# ButoMat.net
KiCad netlist of a schematic drawn in EAGLE
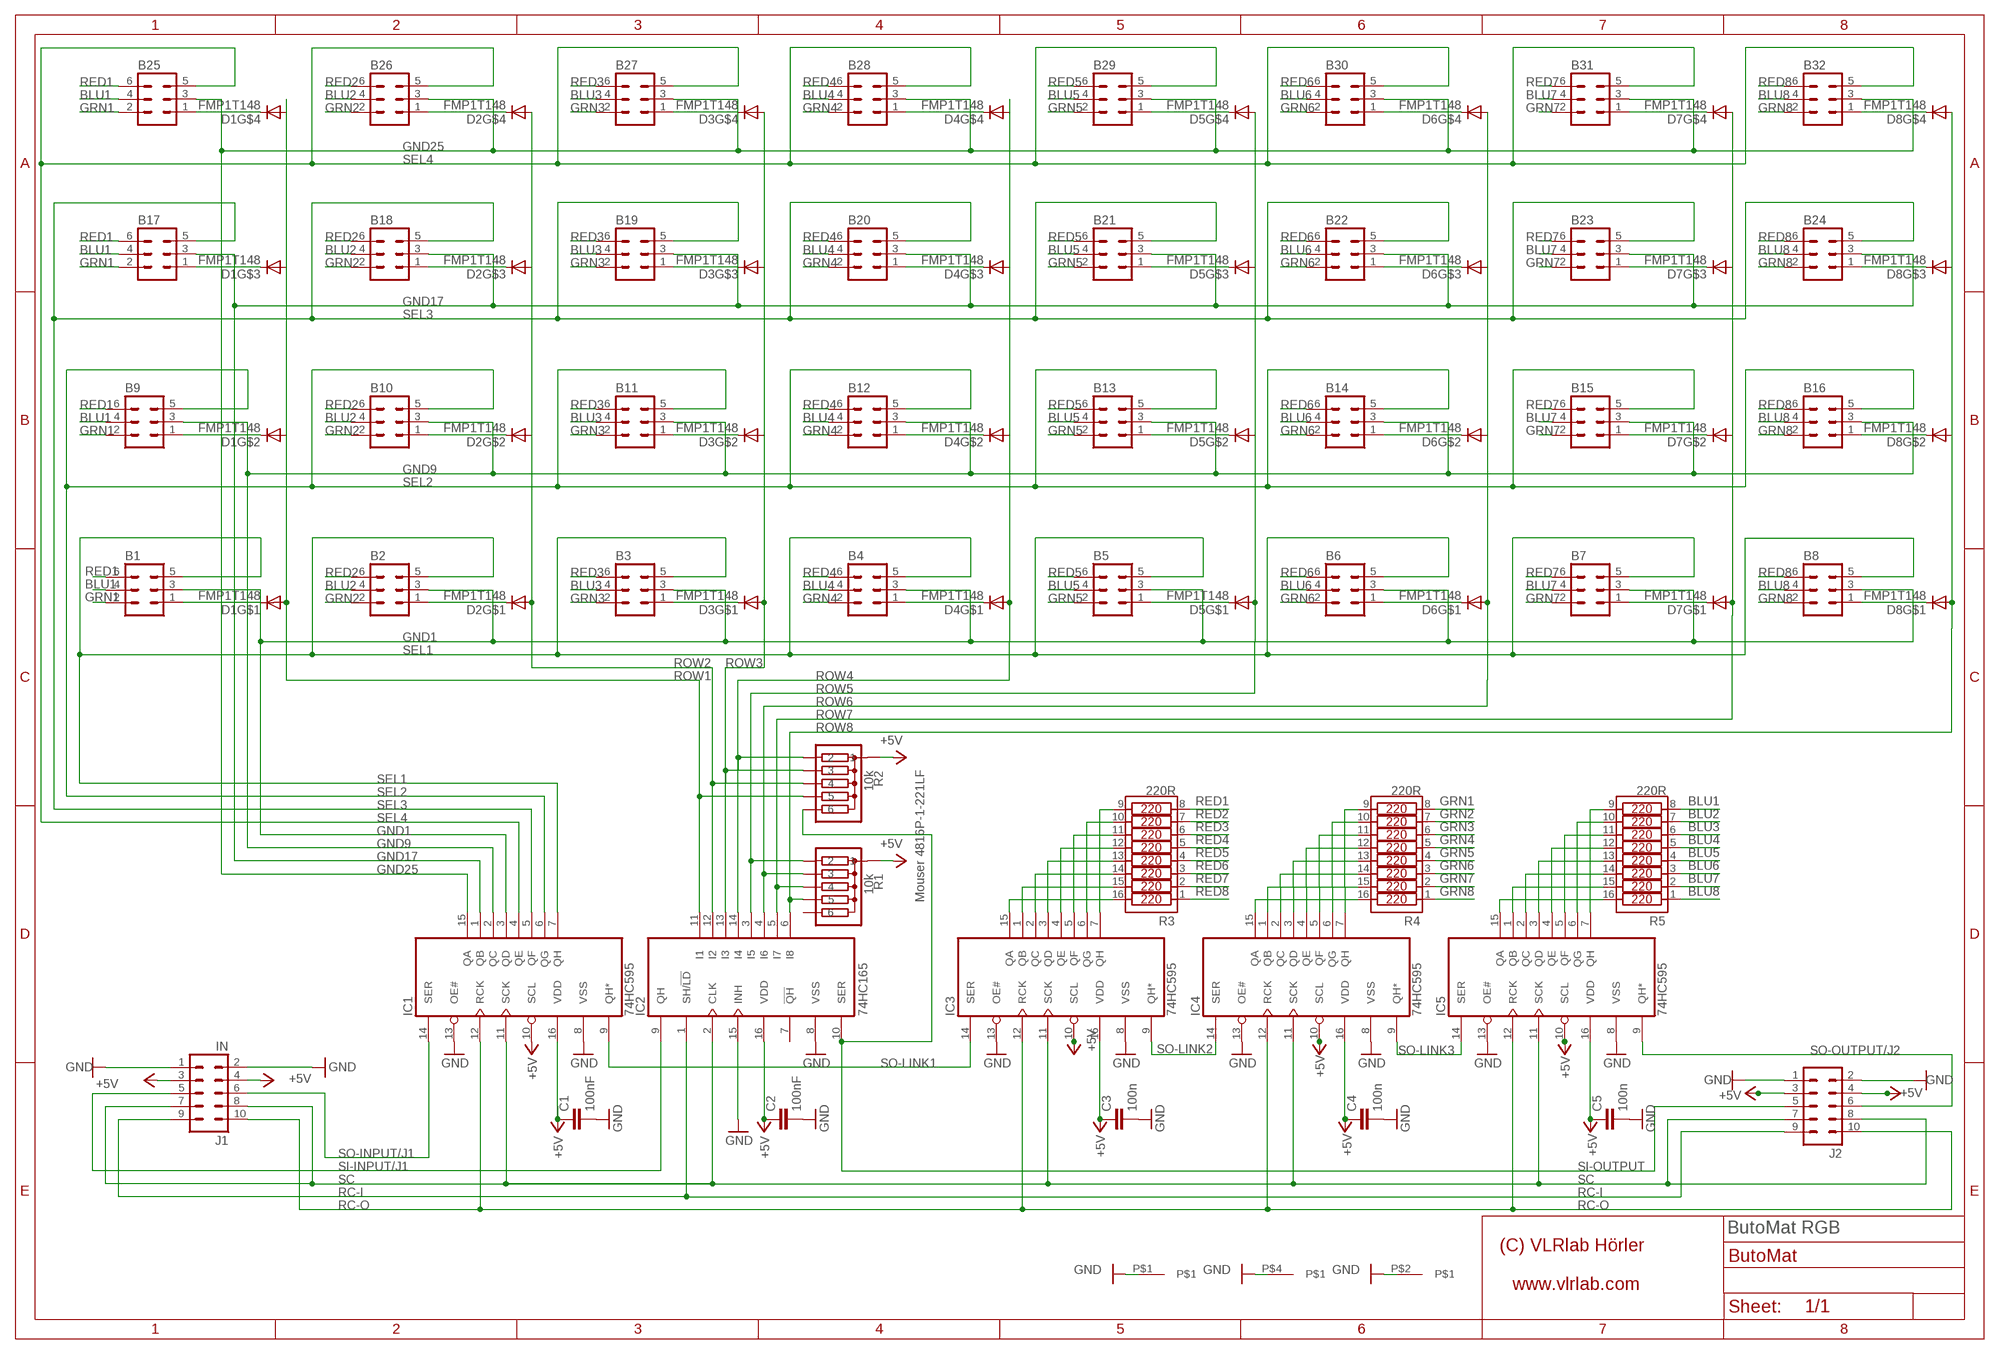
[diagram p0: schematic, sheet 1]

(export (version "E")
  (design (tool "Eeschema 10.0.6"))
  (components
    (comp (ref "B1")
      (value "ML6")
      (footprint "eagle-import:ML6")
      (libsource (lib "eagle-import") (part "ML6"))
    )
    (comp (ref "B2")
      (value "ML6")
      (footprint "eagle-import:ML6")
      (libsource (lib "eagle-import") (part "ML6"))
    )
    (comp (ref "B3")
      (value "ML6")
      (footprint "eagle-import:ML6")
      (libsource (lib "eagle-import") (part "ML6"))
    )
    (comp (ref "B4")
      (value "ML6")
      (footprint "eagle-import:ML6")
      (libsource (lib "eagle-import") (part "ML6"))
    )
    (comp (ref "B5")
      (value "ML6")
      (footprint "eagle-import:ML6")
      (libsource (lib "eagle-import") (part "ML6"))
    )
    (comp (ref "B6")
      (value "ML6")
      (footprint "eagle-import:ML6")
      (libsource (lib "eagle-import") (part "ML6"))
    )
    (comp (ref "B7")
      (value "ML6")
      (footprint "eagle-import:ML6")
      (libsource (lib "eagle-import") (part "ML6"))
    )
    (comp (ref "B8")
      (value "ML6")
      (footprint "eagle-import:ML6")
      (libsource (lib "eagle-import") (part "ML6"))
    )
    (comp (ref "B9")
      (value "ML6")
      (footprint "eagle-import:ML6")
      (libsource (lib "eagle-import") (part "ML6"))
    )
    (comp (ref "B10")
      (value "ML6")
      (footprint "eagle-import:ML6")
      (libsource (lib "eagle-import") (part "ML6"))
    )
    (comp (ref "B11")
      (value "ML6")
      (footprint "eagle-import:ML6")
      (libsource (lib "eagle-import") (part "ML6"))
    )
    (comp (ref "B12")
      (value "ML6")
      (footprint "eagle-import:ML6")
      (libsource (lib "eagle-import") (part "ML6"))
    )
    (comp (ref "B13")
      (value "ML6")
      (footprint "eagle-import:ML6")
      (libsource (lib "eagle-import") (part "ML6"))
    )
    (comp (ref "B14")
      (value "ML6")
      (footprint "eagle-import:ML6")
      (libsource (lib "eagle-import") (part "ML6"))
    )
    (comp (ref "B15")
      (value "ML6")
      (footprint "eagle-import:ML6")
      (libsource (lib "eagle-import") (part "ML6"))
    )
    (comp (ref "B16")
      (value "ML6")
      (footprint "eagle-import:ML6")
      (libsource (lib "eagle-import") (part "ML6"))
    )
    (comp (ref "B17")
      (value "ML6")
      (footprint "eagle-import:ML6")
      (libsource (lib "eagle-import") (part "ML6"))
    )
    (comp (ref "B18")
      (value "ML6")
      (footprint "eagle-import:ML6")
      (libsource (lib "eagle-import") (part "ML6"))
    )
    (comp (ref "B19")
      (value "ML6")
      (footprint "eagle-import:ML6")
      (libsource (lib "eagle-import") (part "ML6"))
    )
    (comp (ref "B20")
      (value "ML6")
      (footprint "eagle-import:ML6")
      (libsource (lib "eagle-import") (part "ML6"))
    )
    (comp (ref "B21")
      (value "ML6")
      (footprint "eagle-import:ML6")
      (libsource (lib "eagle-import") (part "ML6"))
    )
    (comp (ref "B22")
      (value "ML6")
      (footprint "eagle-import:ML6")
      (libsource (lib "eagle-import") (part "ML6"))
    )
    (comp (ref "B23")
      (value "ML6")
      (footprint "eagle-import:ML6")
      (libsource (lib "eagle-import") (part "ML6"))
    )
    (comp (ref "B24")
      (value "ML6")
      (footprint "eagle-import:ML6")
      (libsource (lib "eagle-import") (part "ML6"))
    )
    (comp (ref "B25")
      (value "ML6")
      (footprint "eagle-import:ML6")
      (libsource (lib "eagle-import") (part "ML6"))
    )
    (comp (ref "B26")
      (value "ML6")
      (footprint "eagle-import:ML6")
      (libsource (lib "eagle-import") (part "ML6"))
    )
    (comp (ref "B27")
      (value "ML6")
      (footprint "eagle-import:ML6")
      (libsource (lib "eagle-import") (part "ML6"))
    )
    (comp (ref "B28")
      (value "ML6")
      (footprint "eagle-import:ML6")
      (libsource (lib "eagle-import") (part "ML6"))
    )
    (comp (ref "B29")
      (value "ML6")
      (footprint "eagle-import:ML6")
      (libsource (lib "eagle-import") (part "ML6"))
    )
    (comp (ref "B30")
      (value "ML6")
      (footprint "eagle-import:ML6")
      (libsource (lib "eagle-import") (part "ML6"))
    )
    (comp (ref "B31")
      (value "ML6")
      (footprint "eagle-import:ML6")
      (libsource (lib "eagle-import") (part "ML6"))
    )
    (comp (ref "B32")
      (value "ML6")
      (footprint "eagle-import:ML6")
      (libsource (lib "eagle-import") (part "ML6"))
    )
    (comp (ref "C1")
      (value "100nF")
      (footprint "eagle-import:C025-030X050")
      (libsource (lib "eagle-import") (part "C-EU025-030X050"))
    )
    (comp (ref "C2")
      (value "100nF")
      (footprint "eagle-import:C025-030X050")
      (libsource (lib "eagle-import") (part "C-EU025-030X050"))
    )
    (comp (ref "C3")
      (value "100n")
      (footprint "eagle-import:C025-030X050")
      (libsource (lib "eagle-import") (part "C-EU025-030X050"))
    )
    (comp (ref "C4")
      (value "100n")
      (footprint "eagle-import:C025-030X050")
      (libsource (lib "eagle-import") (part "C-EU025-030X050"))
    )
    (comp (ref "C5")
      (value "100n")
      (footprint "eagle-import:C025-030X050")
      (libsource (lib "eagle-import") (part "C-EU025-030X050"))
    )
    (comp (ref "D1")
      (value "FMP1T148")
      (footprint "eagle-import:SC-74A")
      (libsource (lib "eagle-import") (part "FMP1T148"))
    )
    (comp (ref "D2")
      (value "FMP1T148")
      (footprint "eagle-import:SC-74A")
      (libsource (lib "eagle-import") (part "FMP1T148"))
    )
    (comp (ref "D3")
      (value "FMP1T148")
      (footprint "eagle-import:SC-74A")
      (libsource (lib "eagle-import") (part "FMP1T148"))
    )
    (comp (ref "D4")
      (value "FMP1T148")
      (footprint "eagle-import:SC-74A")
      (libsource (lib "eagle-import") (part "FMP1T148"))
    )
    (comp (ref "D5")
      (value "FMP1T148")
      (footprint "eagle-import:SC-74A")
      (libsource (lib "eagle-import") (part "FMP1T148"))
    )
    (comp (ref "D6")
      (value "FMP1T148")
      (footprint "eagle-import:SC-74A")
      (libsource (lib "eagle-import") (part "FMP1T148"))
    )
    (comp (ref "D7")
      (value "FMP1T148")
      (footprint "eagle-import:SC-74A")
      (libsource (lib "eagle-import") (part "FMP1T148"))
    )
    (comp (ref "D8")
      (value "FMP1T148")
      (footprint "eagle-import:SC-74A")
      (libsource (lib "eagle-import") (part "FMP1T148"))
    )
    (comp (ref "IC1")
      (value "74HC595")
      (footprint "eagle-import:SO16D")
      (libsource (lib "eagle-import") (part "595-541-165-uln2803_74HC595SO16D"))
    )
    (comp (ref "IC2")
      (value "74HC165")
      (footprint "eagle-import:SO16D")
      (libsource (lib "eagle-import") (part "74HC165NSO16D"))
    )
    (comp (ref "IC3")
      (value "74HC595")
      (footprint "eagle-import:SO16D")
      (libsource (lib "eagle-import") (part "595-541-165-uln2803_74HC595SO16D"))
    )
    (comp (ref "IC4")
      (value "74HC595")
      (footprint "eagle-import:SO16D")
      (libsource (lib "eagle-import") (part "595-541-165-uln2803_74HC595SO16D"))
    )
    (comp (ref "IC5")
      (value "74HC595")
      (footprint "eagle-import:SO16D")
      (libsource (lib "eagle-import") (part "595-541-165-uln2803_74HC595SO16D"))
    )
    (comp (ref "J1")
      (value "IN")
      (footprint "eagle-import:ML10")
      (libsource (lib "eagle-import") (part "ML10"))
    )
    (comp (ref "J2")
      (value "ML10")
      (footprint "eagle-import:ML10")
      (libsource (lib "eagle-import") (part "con-ml_ML10"))
    )
    (comp (ref "R1")
      (value "10k")
      (footprint "eagle-import:SIL6")
      (libsource (lib "eagle-import") (part "4306R"))
    )
    (comp (ref "R2")
      (value "10k")
      (footprint "eagle-import:SIL6")
      (libsource (lib "eagle-import") (part "4306R"))
    )
    (comp (ref "R3")
      (value "220R")
      (footprint "eagle-import:SOIC16W")
      (libsource (lib "eagle-import") (part "4816P-1SOIC16W"))
    )
    (comp (ref "R4")
      (value "220R")
      (footprint "eagle-import:SOIC16W")
      (libsource (lib "eagle-import") (part "4816P-1SOIC16W"))
    )
    (comp (ref "R5")
      (value "220R")
      (footprint "eagle-import:SOIC16W")
      (libsource (lib "eagle-import") (part "4816P-1SOIC16W"))
    )
    (comp (ref "U$1")
      (value "MIDIBOX_HALF")
      (footprint "eagle-import:MIDIBOX14X6")
      (libsource (lib "eagle-import") (part "MIDIBOX_HALF"))
    )
  )
  (nets
    (net (code "1") (name "+5V") (class "Default")
      (node (ref "C1") (pin "1") (pinfunction "1_1") (pintype "passive"))
      (node (ref "C2") (pin "1") (pinfunction "1_1") (pintype "passive"))
      (node (ref "C3") (pin "1") (pinfunction "1_1") (pintype "passive"))
      (node (ref "C4") (pin "1") (pinfunction "1_1") (pintype "passive"))
      (node (ref "C5") (pin "1") (pinfunction "1_1") (pintype "passive"))
      (node (ref "IC1") (pin "10") (pinfunction "SCL_10") (pintype "input"))
      (node (ref "IC1") (pin "16") (pinfunction "VDD_16") (pintype "power_in"))
      (node (ref "IC2") (pin "16") (pinfunction "VDD_16") (pintype "power_in"))
      (node (ref "IC3") (pin "10") (pinfunction "SCL_10") (pintype "input"))
      (node (ref "IC3") (pin "16") (pinfunction "VDD_16") (pintype "power_in"))
      (node (ref "IC4") (pin "10") (pinfunction "SCL_10") (pintype "input"))
      (node (ref "IC4") (pin "16") (pinfunction "VDD_16") (pintype "power_in"))
      (node (ref "IC5") (pin "10") (pinfunction "SCL_10") (pintype "input"))
      (node (ref "IC5") (pin "16") (pinfunction "VDD_16") (pintype "power_in"))
      (node (ref "J1") (pin "3") (pinfunction "3_3") (pintype "passive"))
      (node (ref "J1") (pin "4") (pinfunction "4_4") (pintype "passive"))
      (node (ref "J2") (pin "3") (pinfunction "3_3") (pintype "passive"))
      (node (ref "J2") (pin "4") (pinfunction "4_4") (pintype "passive"))
      (node (ref "R1") (pin "1") (pinfunction "1_1") (pintype "passive"))
      (node (ref "R2") (pin "1") (pinfunction "1_1") (pintype "passive"))
    )
    (net (code "2") (name "/BLU1") (class "Default")
      (node (ref "B1") (pin "4") (pinfunction "4_4") (pintype "passive"))
      (node (ref "B17") (pin "4") (pinfunction "4_4") (pintype "passive"))
      (node (ref "B25") (pin "4") (pinfunction "4_4") (pintype "passive"))
      (node (ref "B9") (pin "4") (pinfunction "4_4") (pintype "passive"))
      (node (ref "R5") (pin "8") (pinfunction "P$8_8") (pintype "passive"))
    )
    (net (code "3") (name "/BLU2") (class "Default")
      (node (ref "B10") (pin "4") (pinfunction "4_4") (pintype "passive"))
      (node (ref "B18") (pin "4") (pinfunction "4_4") (pintype "passive"))
      (node (ref "B2") (pin "4") (pinfunction "4_4") (pintype "passive"))
      (node (ref "B26") (pin "4") (pinfunction "4_4") (pintype "passive"))
      (node (ref "R5") (pin "7") (pinfunction "P$7_7") (pintype "passive"))
    )
    (net (code "4") (name "/BLU3") (class "Default")
      (node (ref "B11") (pin "4") (pinfunction "4_4") (pintype "passive"))
      (node (ref "B19") (pin "4") (pinfunction "4_4") (pintype "passive"))
      (node (ref "B27") (pin "4") (pinfunction "4_4") (pintype "passive"))
      (node (ref "B3") (pin "4") (pinfunction "4_4") (pintype "passive"))
      (node (ref "R5") (pin "6") (pinfunction "P$6_6") (pintype "passive"))
    )
    (net (code "5") (name "/BLU4") (class "Default")
      (node (ref "B12") (pin "4") (pinfunction "4_4") (pintype "passive"))
      (node (ref "B20") (pin "4") (pinfunction "4_4") (pintype "passive"))
      (node (ref "B28") (pin "4") (pinfunction "4_4") (pintype "passive"))
      (node (ref "B4") (pin "4") (pinfunction "4_4") (pintype "passive"))
      (node (ref "R5") (pin "5") (pinfunction "P$5_5") (pintype "passive"))
    )
    (net (code "6") (name "/BLU5") (class "Default")
      (node (ref "B13") (pin "4") (pinfunction "4_4") (pintype "passive"))
      (node (ref "B21") (pin "4") (pinfunction "4_4") (pintype "passive"))
      (node (ref "B29") (pin "4") (pinfunction "4_4") (pintype "passive"))
      (node (ref "B5") (pin "4") (pinfunction "4_4") (pintype "passive"))
      (node (ref "R5") (pin "4") (pinfunction "P$4_4") (pintype "passive"))
    )
    (net (code "7") (name "/BLU6") (class "Default")
      (node (ref "B14") (pin "4") (pinfunction "4_4") (pintype "passive"))
      (node (ref "B22") (pin "4") (pinfunction "4_4") (pintype "passive"))
      (node (ref "B30") (pin "4") (pinfunction "4_4") (pintype "passive"))
      (node (ref "B6") (pin "4") (pinfunction "4_4") (pintype "passive"))
      (node (ref "R5") (pin "3") (pinfunction "P$3_3") (pintype "passive"))
    )
    (net (code "8") (name "/BLU7") (class "Default")
      (node (ref "B15") (pin "4") (pinfunction "4_4") (pintype "passive"))
      (node (ref "B23") (pin "4") (pinfunction "4_4") (pintype "passive"))
      (node (ref "B31") (pin "4") (pinfunction "4_4") (pintype "passive"))
      (node (ref "B7") (pin "4") (pinfunction "4_4") (pintype "passive"))
      (node (ref "R5") (pin "2") (pinfunction "P$2_2") (pintype "passive"))
    )
    (net (code "9") (name "/BLU8") (class "Default")
      (node (ref "B16") (pin "4") (pinfunction "4_4") (pintype "passive"))
      (node (ref "B24") (pin "4") (pinfunction "4_4") (pintype "passive"))
      (node (ref "B32") (pin "4") (pinfunction "4_4") (pintype "passive"))
      (node (ref "B8") (pin "4") (pinfunction "4_4") (pintype "passive"))
      (node (ref "R5") (pin "1") (pinfunction "P$1_1") (pintype "passive"))
    )
    (net (code "10") (name "/GND1") (class "Default")
      (node (ref "B1") (pin "3") (pinfunction "3_3") (pintype "passive"))
      (node (ref "B2") (pin "3") (pinfunction "3_3") (pintype "passive"))
      (node (ref "B3") (pin "3") (pinfunction "3_3") (pintype "passive"))
      (node (ref "B4") (pin "3") (pinfunction "3_3") (pintype "passive"))
      (node (ref "B5") (pin "3") (pinfunction "3_3") (pintype "passive"))
      (node (ref "B6") (pin "3") (pinfunction "3_3") (pintype "passive"))
      (node (ref "B7") (pin "3") (pinfunction "3_3") (pintype "passive"))
      (node (ref "B8") (pin "3") (pinfunction "3_3") (pintype "passive"))
      (node (ref "IC1") (pin "3") (pinfunction "QD_3") (pintype "tri_state"))
    )
    (net (code "11") (name "/GND9") (class "Default")
      (node (ref "B10") (pin "3") (pinfunction "3_3") (pintype "passive"))
      (node (ref "B11") (pin "3") (pinfunction "3_3") (pintype "passive"))
      (node (ref "B12") (pin "3") (pinfunction "3_3") (pintype "passive"))
      (node (ref "B13") (pin "3") (pinfunction "3_3") (pintype "passive"))
      (node (ref "B14") (pin "3") (pinfunction "3_3") (pintype "passive"))
      (node (ref "B15") (pin "3") (pinfunction "3_3") (pintype "passive"))
      (node (ref "B16") (pin "3") (pinfunction "3_3") (pintype "passive"))
      (node (ref "B9") (pin "3") (pinfunction "3_3") (pintype "passive"))
      (node (ref "IC1") (pin "2") (pinfunction "QC_2") (pintype "tri_state"))
    )
    (net (code "12") (name "/GND17") (class "Default")
      (node (ref "B17") (pin "3") (pinfunction "3_3") (pintype "passive"))
      (node (ref "B18") (pin "3") (pinfunction "3_3") (pintype "passive"))
      (node (ref "B19") (pin "3") (pinfunction "3_3") (pintype "passive"))
      (node (ref "B20") (pin "3") (pinfunction "3_3") (pintype "passive"))
      (node (ref "B21") (pin "3") (pinfunction "3_3") (pintype "passive"))
      (node (ref "B22") (pin "3") (pinfunction "3_3") (pintype "passive"))
      (node (ref "B23") (pin "3") (pinfunction "3_3") (pintype "passive"))
      (node (ref "B24") (pin "3") (pinfunction "3_3") (pintype "passive"))
      (node (ref "IC1") (pin "1") (pinfunction "QB_1") (pintype "tri_state"))
    )
    (net (code "13") (name "/GND25") (class "Default")
      (node (ref "B25") (pin "3") (pinfunction "3_3") (pintype "passive"))
      (node (ref "B26") (pin "3") (pinfunction "3_3") (pintype "passive"))
      (node (ref "B27") (pin "3") (pinfunction "3_3") (pintype "passive"))
      (node (ref "B28") (pin "3") (pinfunction "3_3") (pintype "passive"))
      (node (ref "B29") (pin "3") (pinfunction "3_3") (pintype "passive"))
      (node (ref "B30") (pin "3") (pinfunction "3_3") (pintype "passive"))
      (node (ref "B31") (pin "3") (pinfunction "3_3") (pintype "passive"))
      (node (ref "B32") (pin "3") (pinfunction "3_3") (pintype "passive"))
      (node (ref "IC1") (pin "15") (pinfunction "QA_15") (pintype "tri_state"))
    )
    (net (code "14") (name "/GRN1") (class "Default")
      (node (ref "B1") (pin "2") (pinfunction "2_2") (pintype "passive"))
      (node (ref "B17") (pin "2") (pinfunction "2_2") (pintype "passive"))
      (node (ref "B25") (pin "2") (pinfunction "2_2") (pintype "passive"))
      (node (ref "B9") (pin "2") (pinfunction "2_2") (pintype "passive"))
      (node (ref "R4") (pin "8") (pinfunction "P$8_8") (pintype "passive"))
    )
    (net (code "15") (name "/GRN2") (class "Default")
      (node (ref "B10") (pin "2") (pinfunction "2_2") (pintype "passive"))
      (node (ref "B18") (pin "2") (pinfunction "2_2") (pintype "passive"))
      (node (ref "B2") (pin "2") (pinfunction "2_2") (pintype "passive"))
      (node (ref "B26") (pin "2") (pinfunction "2_2") (pintype "passive"))
      (node (ref "R4") (pin "7") (pinfunction "P$7_7") (pintype "passive"))
    )
    (net (code "16") (name "/GRN3") (class "Default")
      (node (ref "B11") (pin "2") (pinfunction "2_2") (pintype "passive"))
      (node (ref "B19") (pin "2") (pinfunction "2_2") (pintype "passive"))
      (node (ref "B27") (pin "2") (pinfunction "2_2") (pintype "passive"))
      (node (ref "B3") (pin "2") (pinfunction "2_2") (pintype "passive"))
      (node (ref "R4") (pin "6") (pinfunction "P$6_6") (pintype "passive"))
    )
    (net (code "17") (name "/GRN4") (class "Default")
      (node (ref "B12") (pin "2") (pinfunction "2_2") (pintype "passive"))
      (node (ref "B20") (pin "2") (pinfunction "2_2") (pintype "passive"))
      (node (ref "B28") (pin "2") (pinfunction "2_2") (pintype "passive"))
      (node (ref "B4") (pin "2") (pinfunction "2_2") (pintype "passive"))
      (node (ref "R4") (pin "5") (pinfunction "P$5_5") (pintype "passive"))
    )
    (net (code "18") (name "/GRN5") (class "Default")
      (node (ref "B13") (pin "2") (pinfunction "2_2") (pintype "passive"))
      (node (ref "B21") (pin "2") (pinfunction "2_2") (pintype "passive"))
      (node (ref "B29") (pin "2") (pinfunction "2_2") (pintype "passive"))
      (node (ref "B5") (pin "2") (pinfunction "2_2") (pintype "passive"))
      (node (ref "R4") (pin "4") (pinfunction "P$4_4") (pintype "passive"))
    )
    (net (code "19") (name "/GRN6") (class "Default")
      (node (ref "B14") (pin "2") (pinfunction "2_2") (pintype "passive"))
      (node (ref "B22") (pin "2") (pinfunction "2_2") (pintype "passive"))
      (node (ref "B30") (pin "2") (pinfunction "2_2") (pintype "passive"))
      (node (ref "B6") (pin "2") (pinfunction "2_2") (pintype "passive"))
      (node (ref "R4") (pin "3") (pinfunction "P$3_3") (pintype "passive"))
    )
    (net (code "20") (name "/GRN7") (class "Default")
      (node (ref "B15") (pin "2") (pinfunction "2_2") (pintype "passive"))
      (node (ref "B23") (pin "2") (pinfunction "2_2") (pintype "passive"))
      (node (ref "B31") (pin "2") (pinfunction "2_2") (pintype "passive"))
      (node (ref "B7") (pin "2") (pinfunction "2_2") (pintype "passive"))
      (node (ref "R4") (pin "2") (pinfunction "P$2_2") (pintype "passive"))
    )
    (net (code "21") (name "/GRN8") (class "Default")
      (node (ref "B16") (pin "2") (pinfunction "2_2") (pintype "passive"))
      (node (ref "B24") (pin "2") (pinfunction "2_2") (pintype "passive"))
      (node (ref "B32") (pin "2") (pinfunction "2_2") (pintype "passive"))
      (node (ref "B8") (pin "2") (pinfunction "2_2") (pintype "passive"))
      (node (ref "R4") (pin "1") (pinfunction "P$1_1") (pintype "passive"))
    )
    (net (code "22") (name "/RC-I") (class "Default")
      (node (ref "IC2") (pin "1") (pinfunction "SH/~{LD}_1") (pintype "input"))
      (node (ref "J1") (pin "9") (pinfunction "9_9") (pintype "passive"))
      (node (ref "J2") (pin "9") (pinfunction "9_9") (pintype "passive"))
    )
    (net (code "23") (name "/RC-O") (class "Default")
      (node (ref "IC1") (pin "12") (pinfunction "RCK_12") (pintype "input"))
      (node (ref "IC3") (pin "12") (pinfunction "RCK_12") (pintype "input"))
      (node (ref "IC4") (pin "12") (pinfunction "RCK_12") (pintype "input"))
      (node (ref "IC5") (pin "12") (pinfunction "RCK_12") (pintype "input"))
      (node (ref "J1") (pin "10") (pinfunction "10_10") (pintype "passive"))
      (node (ref "J2") (pin "10") (pinfunction "10_10") (pintype "passive"))
    )
    (net (code "24") (name "/RED1") (class "Default")
      (node (ref "B1") (pin "6") (pinfunction "6_6") (pintype "passive"))
      (node (ref "B17") (pin "6") (pinfunction "6_6") (pintype "passive"))
      (node (ref "B25") (pin "6") (pinfunction "6_6") (pintype "passive"))
      (node (ref "B9") (pin "6") (pinfunction "6_6") (pintype "passive"))
      (node (ref "R3") (pin "8") (pinfunction "P$8_8") (pintype "passive"))
    )
    (net (code "25") (name "/RED2") (class "Default")
      (node (ref "B10") (pin "6") (pinfunction "6_6") (pintype "passive"))
      (node (ref "B18") (pin "6") (pinfunction "6_6") (pintype "passive"))
      (node (ref "B2") (pin "6") (pinfunction "6_6") (pintype "passive"))
      (node (ref "B26") (pin "6") (pinfunction "6_6") (pintype "passive"))
      (node (ref "R3") (pin "7") (pinfunction "P$7_7") (pintype "passive"))
    )
    (net (code "26") (name "/RED3") (class "Default")
      (node (ref "B11") (pin "6") (pinfunction "6_6") (pintype "passive"))
      (node (ref "B19") (pin "6") (pinfunction "6_6") (pintype "passive"))
      (node (ref "B27") (pin "6") (pinfunction "6_6") (pintype "passive"))
      (node (ref "B3") (pin "6") (pinfunction "6_6") (pintype "passive"))
      (node (ref "R3") (pin "6") (pinfunction "P$6_6") (pintype "passive"))
    )
    (net (code "27") (name "/RED4") (class "Default")
      (node (ref "B12") (pin "6") (pinfunction "6_6") (pintype "passive"))
      (node (ref "B20") (pin "6") (pinfunction "6_6") (pintype "passive"))
      (node (ref "B28") (pin "6") (pinfunction "6_6") (pintype "passive"))
      (node (ref "B4") (pin "6") (pinfunction "6_6") (pintype "passive"))
      (node (ref "R3") (pin "5") (pinfunction "P$5_5") (pintype "passive"))
    )
    (net (code "28") (name "/RED5") (class "Default")
      (node (ref "B13") (pin "6") (pinfunction "6_6") (pintype "passive"))
      (node (ref "B21") (pin "6") (pinfunction "6_6") (pintype "passive"))
      (node (ref "B29") (pin "6") (pinfunction "6_6") (pintype "passive"))
      (node (ref "B5") (pin "6") (pinfunction "6_6") (pintype "passive"))
      (node (ref "R3") (pin "4") (pinfunction "P$4_4") (pintype "passive"))
    )
    (net (code "29") (name "/RED6") (class "Default")
      (node (ref "B14") (pin "6") (pinfunction "6_6") (pintype "passive"))
      (node (ref "B22") (pin "6") (pinfunction "6_6") (pintype "passive"))
      (node (ref "B30") (pin "6") (pinfunction "6_6") (pintype "passive"))
      (node (ref "B6") (pin "6") (pinfunction "6_6") (pintype "passive"))
      (node (ref "R3") (pin "3") (pinfunction "P$3_3") (pintype "passive"))
    )
    (net (code "30") (name "/RED7") (class "Default")
      (node (ref "B15") (pin "6") (pinfunction "6_6") (pintype "passive"))
      (node (ref "B23") (pin "6") (pinfunction "6_6") (pintype "passive"))
      (node (ref "B31") (pin "6") (pinfunction "6_6") (pintype "passive"))
      (node (ref "B7") (pin "6") (pinfunction "6_6") (pintype "passive"))
      (node (ref "R3") (pin "2") (pinfunction "P$2_2") (pintype "passive"))
    )
    (net (code "31") (name "/RED8") (class "Default")
      (node (ref "B16") (pin "6") (pinfunction "6_6") (pintype "passive"))
      (node (ref "B24") (pin "6") (pinfunction "6_6") (pintype "passive"))
      (node (ref "B32") (pin "6") (pinfunction "6_6") (pintype "passive"))
      (node (ref "B8") (pin "6") (pinfunction "6_6") (pintype "passive"))
      (node (ref "R3") (pin "1") (pinfunction "P$1_1") (pintype "passive"))
    )
    (net (code "32") (name "/ROW1") (class "Default")
      (node (ref "D1") (pin "ANODE") (pinfunction "A_ANODE") (pintype "passive"))
      (node (ref "IC2") (pin "11") (pinfunction "I1_11") (pintype "input"))
      (node (ref "R2") (pin "5") (pinfunction "5_5") (pintype "passive"))
    )
    (net (code "33") (name "/ROW2") (class "Default")
      (node (ref "D2") (pin "ANODE") (pinfunction "A_ANODE") (pintype "passive"))
      (node (ref "IC2") (pin "12") (pinfunction "I2_12") (pintype "input"))
      (node (ref "R2") (pin "4") (pinfunction "4_4") (pintype "passive"))
    )
    (net (code "34") (name "/ROW3") (class "Default")
      (node (ref "D3") (pin "ANODE") (pinfunction "A_ANODE") (pintype "passive"))
      (node (ref "IC2") (pin "13") (pinfunction "I3_13") (pintype "input"))
      (node (ref "R2") (pin "3") (pinfunction "3_3") (pintype "passive"))
    )
    (net (code "35") (name "/ROW4") (class "Default")
      (node (ref "D4") (pin "ANODE") (pinfunction "A_ANODE") (pintype "passive"))
      (node (ref "IC2") (pin "14") (pinfunction "I4_14") (pintype "input"))
      (node (ref "R2") (pin "2") (pinfunction "2_2") (pintype "passive"))
    )
    (net (code "36") (name "/ROW5") (class "Default")
      (node (ref "D5") (pin "ANODE") (pinfunction "A_ANODE") (pintype "passive"))
      (node (ref "IC2") (pin "3") (pinfunction "I5_3") (pintype "input"))
      (node (ref "R1") (pin "2") (pinfunction "2_2") (pintype "passive"))
    )
    (net (code "37") (name "/ROW6") (class "Default")
      (node (ref "D6") (pin "ANODE") (pinfunction "A_ANODE") (pintype "passive"))
      (node (ref "IC2") (pin "4") (pinfunction "I6_4") (pintype "input"))
      (node (ref "R1") (pin "3") (pinfunction "3_3") (pintype "passive"))
    )
    (net (code "38") (name "/ROW7") (class "Default")
      (node (ref "D7") (pin "ANODE") (pinfunction "A_ANODE") (pintype "passive"))
      (node (ref "IC2") (pin "5") (pinfunction "I7_5") (pintype "input"))
      (node (ref "R1") (pin "4") (pinfunction "4_4") (pintype "passive"))
    )
    (net (code "39") (name "/ROW8") (class "Default")
      (node (ref "D8") (pin "ANODE") (pinfunction "A_ANODE") (pintype "passive"))
      (node (ref "IC2") (pin "6") (pinfunction "I8_6") (pintype "input"))
      (node (ref "R1") (pin "5") (pinfunction "5_5") (pintype "passive"))
    )
    (net (code "40") (name "/SC") (class "Default")
      (node (ref "IC1") (pin "11") (pinfunction "SCK_11") (pintype "input"))
      (node (ref "IC2") (pin "2") (pinfunction "CLK_2") (pintype "input"))
      (node (ref "IC3") (pin "11") (pinfunction "SCK_11") (pintype "input"))
      (node (ref "IC4") (pin "11") (pinfunction "SCK_11") (pintype "input"))
      (node (ref "IC5") (pin "11") (pinfunction "SCK_11") (pintype "input"))
      (node (ref "J1") (pin "7") (pinfunction "7_7") (pintype "passive"))
      (node (ref "J1") (pin "8") (pinfunction "8_8") (pintype "passive"))
      (node (ref "J2") (pin "7") (pinfunction "7_7") (pintype "passive"))
      (node (ref "J2") (pin "8") (pinfunction "8_8") (pintype "passive"))
    )
    (net (code "41") (name "/SEL1") (class "Default")
      (node (ref "B1") (pin "5") (pinfunction "5_5") (pintype "passive"))
      (node (ref "B2") (pin "5") (pinfunction "5_5") (pintype "passive"))
      (node (ref "B3") (pin "5") (pinfunction "5_5") (pintype "passive"))
      (node (ref "B4") (pin "5") (pinfunction "5_5") (pintype "passive"))
      (node (ref "B5") (pin "5") (pinfunction "5_5") (pintype "passive"))
      (node (ref "B6") (pin "5") (pinfunction "5_5") (pintype "passive"))
      (node (ref "B7") (pin "5") (pinfunction "5_5") (pintype "passive"))
      (node (ref "B8") (pin "5") (pinfunction "5_5") (pintype "passive"))
      (node (ref "IC1") (pin "7") (pinfunction "QH_7") (pintype "tri_state"))
    )
    (net (code "42") (name "/SEL2") (class "Default")
      (node (ref "B10") (pin "5") (pinfunction "5_5") (pintype "passive"))
      (node (ref "B11") (pin "5") (pinfunction "5_5") (pintype "passive"))
      (node (ref "B12") (pin "5") (pinfunction "5_5") (pintype "passive"))
      (node (ref "B13") (pin "5") (pinfunction "5_5") (pintype "passive"))
      (node (ref "B14") (pin "5") (pinfunction "5_5") (pintype "passive"))
      (node (ref "B15") (pin "5") (pinfunction "5_5") (pintype "passive"))
      (node (ref "B16") (pin "5") (pinfunction "5_5") (pintype "passive"))
      (node (ref "B9") (pin "5") (pinfunction "5_5") (pintype "passive"))
      (node (ref "IC1") (pin "6") (pinfunction "QG_6") (pintype "tri_state"))
    )
    (net (code "43") (name "/SEL3") (class "Default")
      (node (ref "B17") (pin "5") (pinfunction "5_5") (pintype "passive"))
      (node (ref "B18") (pin "5") (pinfunction "5_5") (pintype "passive"))
      (node (ref "B19") (pin "5") (pinfunction "5_5") (pintype "passive"))
      (node (ref "B20") (pin "5") (pinfunction "5_5") (pintype "passive"))
      (node (ref "B21") (pin "5") (pinfunction "5_5") (pintype "passive"))
      (node (ref "B22") (pin "5") (pinfunction "5_5") (pintype "passive"))
      (node (ref "B23") (pin "5") (pinfunction "5_5") (pintype "passive"))
      (node (ref "B24") (pin "5") (pinfunction "5_5") (pintype "passive"))
      (node (ref "IC1") (pin "5") (pinfunction "QF_5") (pintype "tri_state"))
    )
    (net (code "44") (name "/SEL4") (class "Default")
      (node (ref "B25") (pin "5") (pinfunction "5_5") (pintype "passive"))
      (node (ref "B26") (pin "5") (pinfunction "5_5") (pintype "passive"))
      (node (ref "B27") (pin "5") (pinfunction "5_5") (pintype "passive"))
      (node (ref "B28") (pin "5") (pinfunction "5_5") (pintype "passive"))
      (node (ref "B29") (pin "5") (pinfunction "5_5") (pintype "passive"))
      (node (ref "B30") (pin "5") (pinfunction "5_5") (pintype "passive"))
      (node (ref "B31") (pin "5") (pinfunction "5_5") (pintype "passive"))
      (node (ref "B32") (pin "5") (pinfunction "5_5") (pintype "passive"))
      (node (ref "IC1") (pin "4") (pinfunction "QE_4") (pintype "tri_state"))
    )
    (net (code "45") (name "/SI-INPUT{slash}J1") (class "Default")
      (node (ref "IC2") (pin "9") (pinfunction "QH_9") (pintype "output"))
      (node (ref "J1") (pin "5") (pinfunction "5_5") (pintype "passive"))
    )
    (net (code "46") (name "/SI-OUTPUT") (class "Default")
      (node (ref "IC2") (pin "10") (pinfunction "SER_10") (pintype "input"))
      (node (ref "J2") (pin "5") (pinfunction "5_5") (pintype "passive"))
      (node (ref "R2") (pin "6") (pinfunction "6_6") (pintype "passive"))
    )
    (net (code "47") (name "/SO-INPUT{slash}J1") (class "Default")
      (node (ref "IC1") (pin "14") (pinfunction "SER_14") (pintype "input"))
      (node (ref "J1") (pin "6") (pinfunction "6_6") (pintype "passive"))
    )
    (net (code "48") (name "/SO-LINK1") (class "Default")
      (node (ref "IC1") (pin "9") (pinfunction "QH*_9") (pintype "tri_state"))
      (node (ref "IC3") (pin "14") (pinfunction "SER_14") (pintype "input"))
    )
    (net (code "49") (name "/SO-LINK2") (class "Default")
      (node (ref "IC3") (pin "9") (pinfunction "QH*_9") (pintype "tri_state"))
      (node (ref "IC4") (pin "14") (pinfunction "SER_14") (pintype "input"))
    )
    (net (code "50") (name "/SO-LINK3") (class "Default")
      (node (ref "IC4") (pin "9") (pinfunction "QH*_9") (pintype "tri_state"))
      (node (ref "IC5") (pin "14") (pinfunction "SER_14") (pintype "input"))
    )
    (net (code "51") (name "/SO-OUTPUT{slash}J2") (class "Default")
      (node (ref "IC5") (pin "9") (pinfunction "QH*_9") (pintype "tri_state"))
      (node (ref "J2") (pin "6") (pinfunction "6_6") (pintype "passive"))
    )
    (net (code "52") (name "GND") (class "Default")
      (node (ref "C1") (pin "2") (pinfunction "2_2") (pintype "passive"))
      (node (ref "C2") (pin "2") (pinfunction "2_2") (pintype "passive"))
      (node (ref "C3") (pin "2") (pinfunction "2_2") (pintype "passive"))
      (node (ref "C4") (pin "2") (pinfunction "2_2") (pintype "passive"))
      (node (ref "C5") (pin "2") (pinfunction "2_2") (pintype "passive"))
      (node (ref "IC1") (pin "13") (pinfunction "OE#_13") (pintype "input"))
      (node (ref "IC1") (pin "8") (pinfunction "VSS_8") (pintype "power_in"))
      (node (ref "IC2") (pin "15") (pinfunction "INH_15") (pintype "input"))
      (node (ref "IC2") (pin "8") (pinfunction "VSS_8") (pintype "power_in"))
      (node (ref "IC3") (pin "13") (pinfunction "OE#_13") (pintype "input"))
      (node (ref "IC3") (pin "8") (pinfunction "VSS_8") (pintype "power_in"))
      (node (ref "IC4") (pin "13") (pinfunction "OE#_13") (pintype "input"))
      (node (ref "IC4") (pin "8") (pinfunction "VSS_8") (pintype "power_in"))
      (node (ref "IC5") (pin "13") (pinfunction "OE#_13") (pintype "input"))
      (node (ref "IC5") (pin "8") (pinfunction "VSS_8") (pintype "power_in"))
      (node (ref "J1") (pin "1") (pinfunction "1_1") (pintype "passive"))
      (node (ref "J1") (pin "2") (pinfunction "2_2") (pintype "passive"))
      (node (ref "J2") (pin "1") (pinfunction "1_1") (pintype "passive"))
      (node (ref "J2") (pin "2") (pinfunction "2_2") (pintype "passive"))
      (node (ref "U$1") (pin "P$1") (pinfunction "P$1_P$1") (pintype "bidirectional"))
      (node (ref "U$1") (pin "P$2") (pinfunction "P$1_P$2") (pintype "bidirectional"))
      (node (ref "U$1") (pin "P$4") (pinfunction "P$1_P$4") (pintype "bidirectional"))
    )
    (net (code "53") (name "Net-(D1A-C)") (class "Default")
      (node (ref "B1") (pin "1") (pinfunction "1_1") (pintype "passive"))
      (node (ref "D1") (pin "K$1") (pinfunction "C_K$1") (pintype "passive"))
    )
    (net (code "54") (name "Net-(D1B-C)") (class "Default")
      (node (ref "B9") (pin "1") (pinfunction "1_1") (pintype "passive"))
      (node (ref "D1") (pin "K$2") (pinfunction "C_K$2") (pintype "passive"))
    )
    (net (code "55") (name "Net-(D1C-C)") (class "Default")
      (node (ref "B17") (pin "1") (pinfunction "1_1") (pintype "passive"))
      (node (ref "D1") (pin "K$3") (pinfunction "C_K$3") (pintype "passive"))
    )
    (net (code "56") (name "Net-(D1D-C)") (class "Default")
      (node (ref "B25") (pin "1") (pinfunction "1_1") (pintype "passive"))
      (node (ref "D1") (pin "K$4") (pinfunction "C_K$4") (pintype "passive"))
    )
    (net (code "57") (name "Net-(D2A-C)") (class "Default")
      (node (ref "B2") (pin "1") (pinfunction "1_1") (pintype "passive"))
      (node (ref "D2") (pin "K$1") (pinfunction "C_K$1") (pintype "passive"))
    )
    (net (code "58") (name "Net-(D2B-C)") (class "Default")
      (node (ref "B10") (pin "1") (pinfunction "1_1") (pintype "passive"))
      (node (ref "D2") (pin "K$2") (pinfunction "C_K$2") (pintype "passive"))
    )
    (net (code "59") (name "Net-(D2C-C)") (class "Default")
      (node (ref "B18") (pin "1") (pinfunction "1_1") (pintype "passive"))
      (node (ref "D2") (pin "K$3") (pinfunction "C_K$3") (pintype "passive"))
    )
    (net (code "60") (name "Net-(D2D-C)") (class "Default")
      (node (ref "B26") (pin "1") (pinfunction "1_1") (pintype "passive"))
      (node (ref "D2") (pin "K$4") (pinfunction "C_K$4") (pintype "passive"))
    )
    (net (code "61") (name "Net-(D3A-C)") (class "Default")
      (node (ref "B3") (pin "1") (pinfunction "1_1") (pintype "passive"))
      (node (ref "D3") (pin "K$1") (pinfunction "C_K$1") (pintype "passive"))
    )
    (net (code "62") (name "Net-(D3B-C)") (class "Default")
      (node (ref "B11") (pin "1") (pinfunction "1_1") (pintype "passive"))
      (node (ref "D3") (pin "K$2") (pinfunction "C_K$2") (pintype "passive"))
    )
    (net (code "63") (name "Net-(D3C-C)") (class "Default")
      (node (ref "B19") (pin "1") (pinfunction "1_1") (pintype "passive"))
      (node (ref "D3") (pin "K$3") (pinfunction "C_K$3") (pintype "passive"))
    )
    (net (code "64") (name "Net-(D3D-C)") (class "Default")
      (node (ref "B27") (pin "1") (pinfunction "1_1") (pintype "passive"))
      (node (ref "D3") (pin "K$4") (pinfunction "C_K$4") (pintype "passive"))
    )
    (net (code "65") (name "Net-(D4A-C)") (class "Default")
      (node (ref "B4") (pin "1") (pinfunction "1_1") (pintype "passive"))
      (node (ref "D4") (pin "K$1") (pinfunction "C_K$1") (pintype "passive"))
    )
    (net (code "66") (name "Net-(D4B-C)") (class "Default")
      (node (ref "B12") (pin "1") (pinfunction "1_1") (pintype "passive"))
      (node (ref "D4") (pin "K$2") (pinfunction "C_K$2") (pintype "passive"))
    )
    (net (code "67") (name "Net-(D4C-C)") (class "Default")
      (node (ref "B20") (pin "1") (pinfunction "1_1") (pintype "passive"))
      (node (ref "D4") (pin "K$3") (pinfunction "C_K$3") (pintype "passive"))
    )
    (net (code "68") (name "Net-(D4D-C)") (class "Default")
      (node (ref "B28") (pin "1") (pinfunction "1_1") (pintype "passive"))
      (node (ref "D4") (pin "K$4") (pinfunction "C_K$4") (pintype "passive"))
    )
    (net (code "69") (name "Net-(D5A-C)") (class "Default")
      (node (ref "B5") (pin "1") (pinfunction "1_1") (pintype "passive"))
      (node (ref "D5") (pin "K$1") (pinfunction "C_K$1") (pintype "passive"))
    )
    (net (code "70") (name "Net-(D5B-C)") (class "Default")
      (node (ref "B13") (pin "1") (pinfunction "1_1") (pintype "passive"))
      (node (ref "D5") (pin "K$2") (pinfunction "C_K$2") (pintype "passive"))
    )
    (net (code "71") (name "Net-(D5C-C)") (class "Default")
      (node (ref "B21") (pin "1") (pinfunction "1_1") (pintype "passive"))
      (node (ref "D5") (pin "K$3") (pinfunction "C_K$3") (pintype "passive"))
    )
    (net (code "72") (name "Net-(D5D-C)") (class "Default")
      (node (ref "B29") (pin "1") (pinfunction "1_1") (pintype "passive"))
      (node (ref "D5") (pin "K$4") (pinfunction "C_K$4") (pintype "passive"))
    )
    (net (code "73") (name "Net-(D6A-C)") (class "Default")
      (node (ref "B6") (pin "1") (pinfunction "1_1") (pintype "passive"))
      (node (ref "D6") (pin "K$1") (pinfunction "C_K$1") (pintype "passive"))
    )
    (net (code "74") (name "Net-(D6B-C)") (class "Default")
      (node (ref "B14") (pin "1") (pinfunction "1_1") (pintype "passive"))
      (node (ref "D6") (pin "K$2") (pinfunction "C_K$2") (pintype "passive"))
    )
    (net (code "75") (name "Net-(D6C-C)") (class "Default")
      (node (ref "B22") (pin "1") (pinfunction "1_1") (pintype "passive"))
      (node (ref "D6") (pin "K$3") (pinfunction "C_K$3") (pintype "passive"))
    )
    (net (code "76") (name "Net-(D6D-C)") (class "Default")
      (node (ref "B30") (pin "1") (pinfunction "1_1") (pintype "passive"))
      (node (ref "D6") (pin "K$4") (pinfunction "C_K$4") (pintype "passive"))
    )
    (net (code "77") (name "Net-(D7A-C)") (class "Default")
      (node (ref "B7") (pin "1") (pinfunction "1_1") (pintype "passive"))
      (node (ref "D7") (pin "K$1") (pinfunction "C_K$1") (pintype "passive"))
    )
    (net (code "78") (name "Net-(D7B-C)") (class "Default")
      (node (ref "B15") (pin "1") (pinfunction "1_1") (pintype "passive"))
      (node (ref "D7") (pin "K$2") (pinfunction "C_K$2") (pintype "passive"))
    )
    (net (code "79") (name "Net-(D7C-C)") (class "Default")
      (node (ref "B23") (pin "1") (pinfunction "1_1") (pintype "passive"))
      (node (ref "D7") (pin "K$3") (pinfunction "C_K$3") (pintype "passive"))
    )
    (net (code "80") (name "Net-(D7D-C)") (class "Default")
      (node (ref "B31") (pin "1") (pinfunction "1_1") (pintype "passive"))
      (node (ref "D7") (pin "K$4") (pinfunction "C_K$4") (pintype "passive"))
    )
    (net (code "81") (name "Net-(D8A-C)") (class "Default")
      (node (ref "B8") (pin "1") (pinfunction "1_1") (pintype "passive"))
      (node (ref "D8") (pin "K$1") (pinfunction "C_K$1") (pintype "passive"))
    )
    (net (code "82") (name "Net-(D8B-C)") (class "Default")
      (node (ref "B16") (pin "1") (pinfunction "1_1") (pintype "passive"))
      (node (ref "D8") (pin "K$2") (pinfunction "C_K$2") (pintype "passive"))
    )
    (net (code "83") (name "Net-(D8C-C)") (class "Default")
      (node (ref "B24") (pin "1") (pinfunction "1_1") (pintype "passive"))
      (node (ref "D8") (pin "K$3") (pinfunction "C_K$3") (pintype "passive"))
    )
    (net (code "84") (name "Net-(D8D-C)") (class "Default")
      (node (ref "B32") (pin "1") (pinfunction "1_1") (pintype "passive"))
      (node (ref "D8") (pin "K$4") (pinfunction "C_K$4") (pintype "passive"))
    )
    (net (code "85") (name "Net-(IC3-QA)") (class "Default")
      (node (ref "IC3") (pin "15") (pinfunction "QA_15") (pintype "tri_state"))
      (node (ref "R3") (pin "16") (pinfunction "P$16_16") (pintype "passive"))
    )
    (net (code "86") (name "Net-(IC3-QB)") (class "Default")
      (node (ref "IC3") (pin "1") (pinfunction "QB_1") (pintype "tri_state"))
      (node (ref "R3") (pin "15") (pinfunction "P$15_15") (pintype "passive"))
    )
    (net (code "87") (name "Net-(IC3-QC)") (class "Default")
      (node (ref "IC3") (pin "2") (pinfunction "QC_2") (pintype "tri_state"))
      (node (ref "R3") (pin "14") (pinfunction "P$14_14") (pintype "passive"))
    )
    (net (code "88") (name "Net-(IC3-QD)") (class "Default")
      (node (ref "IC3") (pin "3") (pinfunction "QD_3") (pintype "tri_state"))
      (node (ref "R3") (pin "13") (pinfunction "P$13_13") (pintype "passive"))
    )
    (net (code "89") (name "Net-(IC3-QE)") (class "Default")
      (node (ref "IC3") (pin "4") (pinfunction "QE_4") (pintype "tri_state"))
      (node (ref "R3") (pin "12") (pinfunction "P$12_12") (pintype "passive"))
    )
    (net (code "90") (name "Net-(IC3-QF)") (class "Default")
      (node (ref "IC3") (pin "5") (pinfunction "QF_5") (pintype "tri_state"))
      (node (ref "R3") (pin "11") (pinfunction "P$11_11") (pintype "passive"))
    )
    (net (code "91") (name "Net-(IC3-QG)") (class "Default")
      (node (ref "IC3") (pin "6") (pinfunction "QG_6") (pintype "tri_state"))
      (node (ref "R3") (pin "10") (pinfunction "P$10_10") (pintype "passive"))
    )
    (net (code "92") (name "Net-(IC3-QH)") (class "Default")
      (node (ref "IC3") (pin "7") (pinfunction "QH_7") (pintype "tri_state"))
      (node (ref "R3") (pin "9") (pinfunction "P$9_9") (pintype "passive"))
    )
    (net (code "93") (name "Net-(IC4-QA)") (class "Default")
      (node (ref "IC4") (pin "15") (pinfunction "QA_15") (pintype "tri_state"))
      (node (ref "R4") (pin "16") (pinfunction "P$16_16") (pintype "passive"))
    )
    (net (code "94") (name "Net-(IC4-QB)") (class "Default")
      (node (ref "IC4") (pin "1") (pinfunction "QB_1") (pintype "tri_state"))
      (node (ref "R4") (pin "15") (pinfunction "P$15_15") (pintype "passive"))
    )
    (net (code "95") (name "Net-(IC4-QC)") (class "Default")
      (node (ref "IC4") (pin "2") (pinfunction "QC_2") (pintype "tri_state"))
      (node (ref "R4") (pin "14") (pinfunction "P$14_14") (pintype "passive"))
    )
    (net (code "96") (name "Net-(IC4-QD)") (class "Default")
      (node (ref "IC4") (pin "3") (pinfunction "QD_3") (pintype "tri_state"))
      (node (ref "R4") (pin "13") (pinfunction "P$13_13") (pintype "passive"))
    )
    (net (code "97") (name "Net-(IC4-QE)") (class "Default")
      (node (ref "IC4") (pin "4") (pinfunction "QE_4") (pintype "tri_state"))
      (node (ref "R4") (pin "12") (pinfunction "P$12_12") (pintype "passive"))
    )
    (net (code "98") (name "Net-(IC4-QF)") (class "Default")
      (node (ref "IC4") (pin "5") (pinfunction "QF_5") (pintype "tri_state"))
      (node (ref "R4") (pin "11") (pinfunction "P$11_11") (pintype "passive"))
    )
    (net (code "99") (name "Net-(IC4-QG)") (class "Default")
      (node (ref "IC4") (pin "6") (pinfunction "QG_6") (pintype "tri_state"))
      (node (ref "R4") (pin "10") (pinfunction "P$10_10") (pintype "passive"))
    )
    (net (code "100") (name "Net-(IC4-QH)") (class "Default")
      (node (ref "IC4") (pin "7") (pinfunction "QH_7") (pintype "tri_state"))
      (node (ref "R4") (pin "9") (pinfunction "P$9_9") (pintype "passive"))
    )
    (net (code "101") (name "Net-(IC5-QA)") (class "Default")
      (node (ref "IC5") (pin "15") (pinfunction "QA_15") (pintype "tri_state"))
      (node (ref "R5") (pin "16") (pinfunction "P$16_16") (pintype "passive"))
    )
    (net (code "102") (name "Net-(IC5-QB)") (class "Default")
      (node (ref "IC5") (pin "1") (pinfunction "QB_1") (pintype "tri_state"))
      (node (ref "R5") (pin "15") (pinfunction "P$15_15") (pintype "passive"))
    )
    (net (code "103") (name "Net-(IC5-QC)") (class "Default")
      (node (ref "IC5") (pin "2") (pinfunction "QC_2") (pintype "tri_state"))
      (node (ref "R5") (pin "14") (pinfunction "P$14_14") (pintype "passive"))
    )
    (net (code "104") (name "Net-(IC5-QD)") (class "Default")
      (node (ref "IC5") (pin "3") (pinfunction "QD_3") (pintype "tri_state"))
      (node (ref "R5") (pin "13") (pinfunction "P$13_13") (pintype "passive"))
    )
    (net (code "105") (name "Net-(IC5-QE)") (class "Default")
      (node (ref "IC5") (pin "4") (pinfunction "QE_4") (pintype "tri_state"))
      (node (ref "R5") (pin "12") (pinfunction "P$12_12") (pintype "passive"))
    )
    (net (code "106") (name "Net-(IC5-QF)") (class "Default")
      (node (ref "IC5") (pin "5") (pinfunction "QF_5") (pintype "tri_state"))
      (node (ref "R5") (pin "11") (pinfunction "P$11_11") (pintype "passive"))
    )
    (net (code "107") (name "Net-(IC5-QG)") (class "Default")
      (node (ref "IC5") (pin "6") (pinfunction "QG_6") (pintype "tri_state"))
      (node (ref "R5") (pin "10") (pinfunction "P$10_10") (pintype "passive"))
    )
    (net (code "108") (name "Net-(IC5-QH)") (class "Default")
      (node (ref "IC5") (pin "7") (pinfunction "QH_7") (pintype "tri_state"))
      (node (ref "R5") (pin "9") (pinfunction "P$9_9") (pintype "passive"))
    )
    (net (code "109") (name "unconnected-(IC2-~{QH}-Pad7)") (class "Default")
      (node (ref "IC2") (pin "7") (pinfunction "~{QH}_7") (pintype "output"))
    )
    (net (code "110") (name "unconnected-(R1-Pad6)") (class "Default")
      (node (ref "R1") (pin "6") (pinfunction "6_6") (pintype "passive"))
    )
  )
)
